# displaykort.net
KiCad netlist of a schematic drawn in Altium Designer
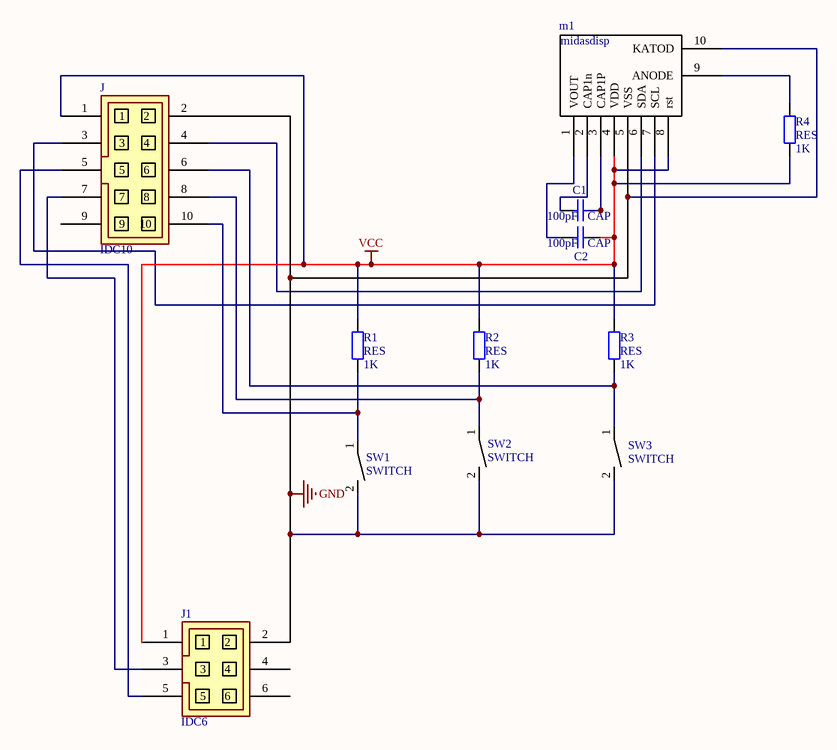
[diagram p0: displaykort.SchDoc]

(export (version "E")
  (design (tool "Eeschema 10.0.6"))
  (components
    (comp (ref "C1")
      (value "CAP")
      (footprint "CAPC2012X11M")
      (description "Capacitor")
      (fields (field (name "ALTIUM_VALUE") "100pF") (field (name "PUBLISHER") "Altium Limited"))
      (libsource (lib "std") (part "CAP"))
    )
    (comp (ref "C2")
      (value "CAP")
      (footprint "CAPC2012X11M")
      (description "Capacitor")
      (fields (field (name "ALTIUM_VALUE") "100pF") (field (name "PUBLISHER") "Altium Limited"))
      (libsource (lib "std") (part "CAP"))
    )
    (comp (ref "J")
      (value "IDC10")
      (footprint "IDC10")
      (description "10pin IDC connector")
      (libsource (lib "std") (part "IDC10"))
    )
    (comp (ref "J1")
      (value "IDC6")
      (footprint "IDC6")
      (description "6pin IDC connector")
      (libsource (lib "std") (part "IDC6"))
    )
    (comp (ref "m1")
      (value "midasdisp")
      (footprint "PCBComponent_1")
      (libsource (lib "MIDOSDISP") (part "midasdisp"))
    )
    (comp (ref "R1")
      (value "RES")
      (footprint "RESC2012X07M")
      (description "Resistor")
      (fields (field (name "ALTIUM_VALUE") "1K") (field (name "PUBLISHER") "Altium Limited"))
      (libsource (lib "std") (part "RES"))
    )
    (comp (ref "R2")
      (value "RES")
      (footprint "RESC2012X07M")
      (description "Resistor")
      (fields (field (name "ALTIUM_VALUE") "1K") (field (name "PUBLISHER") "Altium Limited"))
      (libsource (lib "std") (part "RES"))
    )
    (comp (ref "R3")
      (value "RES")
      (footprint "RESC2012X07M")
      (description "Resistor")
      (fields (field (name "ALTIUM_VALUE") "1K") (field (name "PUBLISHER") "Altium Limited"))
      (libsource (lib "std") (part "RES"))
    )
    (comp (ref "R4")
      (value "RES")
      (footprint "RESC2012X07M")
      (description "Resistor")
      (fields (field (name "ALTIUM_VALUE") "1K") (field (name "PUBLISHER") "Altium Limited"))
      (libsource (lib "std") (part "RES"))
    )
    (comp (ref "SW1")
      (value "SWITCH")
      (footprint "Switch_pad")
      (description "Switch")
      (libsource (lib "std") (part "Switch"))
    )
    (comp (ref "SW2")
      (value "SWITCH")
      (footprint "Switch_pad")
      (description "Switch")
      (libsource (lib "std") (part "Switch"))
    )
    (comp (ref "SW3")
      (value "SWITCH")
      (footprint "Switch_pad")
      (description "Switch")
      (libsource (lib "std") (part "Switch"))
    )
  )
  (nets
    (net (code "1") (name "GND") (class "Default")
      (node (ref "J") (pin "2") (pinfunction "2_2") (pintype "passive"))
      (node (ref "J1") (pin "2") (pinfunction "2_2") (pintype "passive"))
      (node (ref "SW1") (pin "2") (pinfunction "2_2") (pintype "passive"))
      (node (ref "SW2") (pin "2") (pinfunction "2_2") (pintype "passive"))
      (node (ref "SW3") (pin "2") (pinfunction "2_2") (pintype "passive"))
      (node (ref "m1") (pin "10") (pinfunction "KATOD_10") (pintype "passive"))
      (node (ref "m1") (pin "5") (pinfunction "VSS_5") (pintype "passive"))
    )
    (net (code "2") (name "Net-(J-Pad5)") (class "Default")
      (node (ref "J") (pin "5") (pinfunction "5_5") (pintype "passive"))
      (node (ref "J1") (pin "5") (pinfunction "5_5") (pintype "passive"))
    )
    (net (code "3") (name "Net-(J-Pad6)") (class "Default")
      (node (ref "J") (pin "6") (pinfunction "6_6") (pintype "passive"))
      (node (ref "R3") (pin "1") (pinfunction "1_1") (pintype "passive"))
      (node (ref "SW3") (pin "1") (pinfunction "1_1") (pintype "passive"))
    )
    (net (code "4") (name "Net-(J-Pad7)") (class "Default")
      (node (ref "J") (pin "7") (pinfunction "7_7") (pintype "passive"))
      (node (ref "J1") (pin "3") (pinfunction "3_3") (pintype "passive"))
    )
    (net (code "5") (name "Net-(J-Pad8)") (class "Default")
      (node (ref "J") (pin "8") (pinfunction "8_8") (pintype "passive"))
      (node (ref "R2") (pin "1") (pinfunction "1_1") (pintype "passive"))
      (node (ref "SW2") (pin "1") (pinfunction "1_1") (pintype "passive"))
    )
    (net (code "6") (name "Net-(J-Pad10)") (class "Default")
      (node (ref "J") (pin "10") (pinfunction "10_10") (pintype "passive"))
      (node (ref "R1") (pin "1") (pinfunction "1_1") (pintype "passive"))
      (node (ref "SW1") (pin "1") (pinfunction "1_1") (pintype "passive"))
    )
    (net (code "7") (name "Net-(m1-ANODE)") (class "Default")
      (node (ref "R4") (pin "2") (pinfunction "2_2") (pintype "passive"))
      (node (ref "m1") (pin "9") (pinfunction "ANODE_9") (pintype "passive"))
    )
    (net (code "8") (name "Net-(m1-CAP1P)") (class "Default")
      (node (ref "C1") (pin "2") (pinfunction "2_2") (pintype "passive"))
      (node (ref "m1") (pin "3") (pinfunction "CAP1P_3") (pintype "passive"))
    )
    (net (code "9") (name "Net-(m1-CAP1n)") (class "Default")
      (node (ref "C1") (pin "1") (pinfunction "1_1") (pintype "passive"))
      (node (ref "m1") (pin "2") (pinfunction "CAP1n_2") (pintype "passive"))
    )
    (net (code "10") (name "Net-(m1-SCL)") (class "Default")
      (node (ref "J") (pin "3") (pinfunction "3_3") (pintype "passive"))
      (node (ref "m1") (pin "7") (pinfunction "SCL_7") (pintype "passive"))
    )
    (net (code "11") (name "Net-(m1-SDA)") (class "Default")
      (node (ref "J") (pin "4") (pinfunction "4_4") (pintype "passive"))
      (node (ref "m1") (pin "6") (pinfunction "SDA_6") (pintype "passive"))
    )
    (net (code "12") (name "Net-(m1-VOUT)") (class "Default")
      (node (ref "C2") (pin "1") (pinfunction "1_1") (pintype "passive"))
      (node (ref "m1") (pin "1") (pinfunction "VOUT_1") (pintype "passive"))
    )
    (net (code "13") (name "VCC") (class "Default")
      (node (ref "C2") (pin "2") (pinfunction "2_2") (pintype "passive"))
      (node (ref "J") (pin "1") (pinfunction "1_1") (pintype "passive"))
      (node (ref "J1") (pin "1") (pinfunction "1_1") (pintype "passive"))
      (node (ref "R1") (pin "2") (pinfunction "2_2") (pintype "passive"))
      (node (ref "R2") (pin "2") (pinfunction "2_2") (pintype "passive"))
      (node (ref "R3") (pin "2") (pinfunction "2_2") (pintype "passive"))
      (node (ref "R4") (pin "1") (pinfunction "1_1") (pintype "passive"))
      (node (ref "m1") (pin "4") (pinfunction "VDD_4") (pintype "passive"))
      (node (ref "m1") (pin "8") (pinfunction "rst_8") (pintype "passive"))
    )
    (net (code "14") (name "unconnected-(J-Pad9)") (class "Default")
      (node (ref "J") (pin "9") (pinfunction "9_9") (pintype "passive"))
    )
    (net (code "15") (name "unconnected-(J1-Pad4)") (class "Default")
      (node (ref "J1") (pin "4") (pinfunction "4_4") (pintype "passive"))
    )
    (net (code "16") (name "unconnected-(J1-Pad6)") (class "Default")
      (node (ref "J1") (pin "6") (pinfunction "6_6") (pintype "passive"))
    )
  )
)
